# OpAmp_CCCV_Regulator_2026_1_2_A.net
KiCad netlist of a schematic drawn in EAGLE
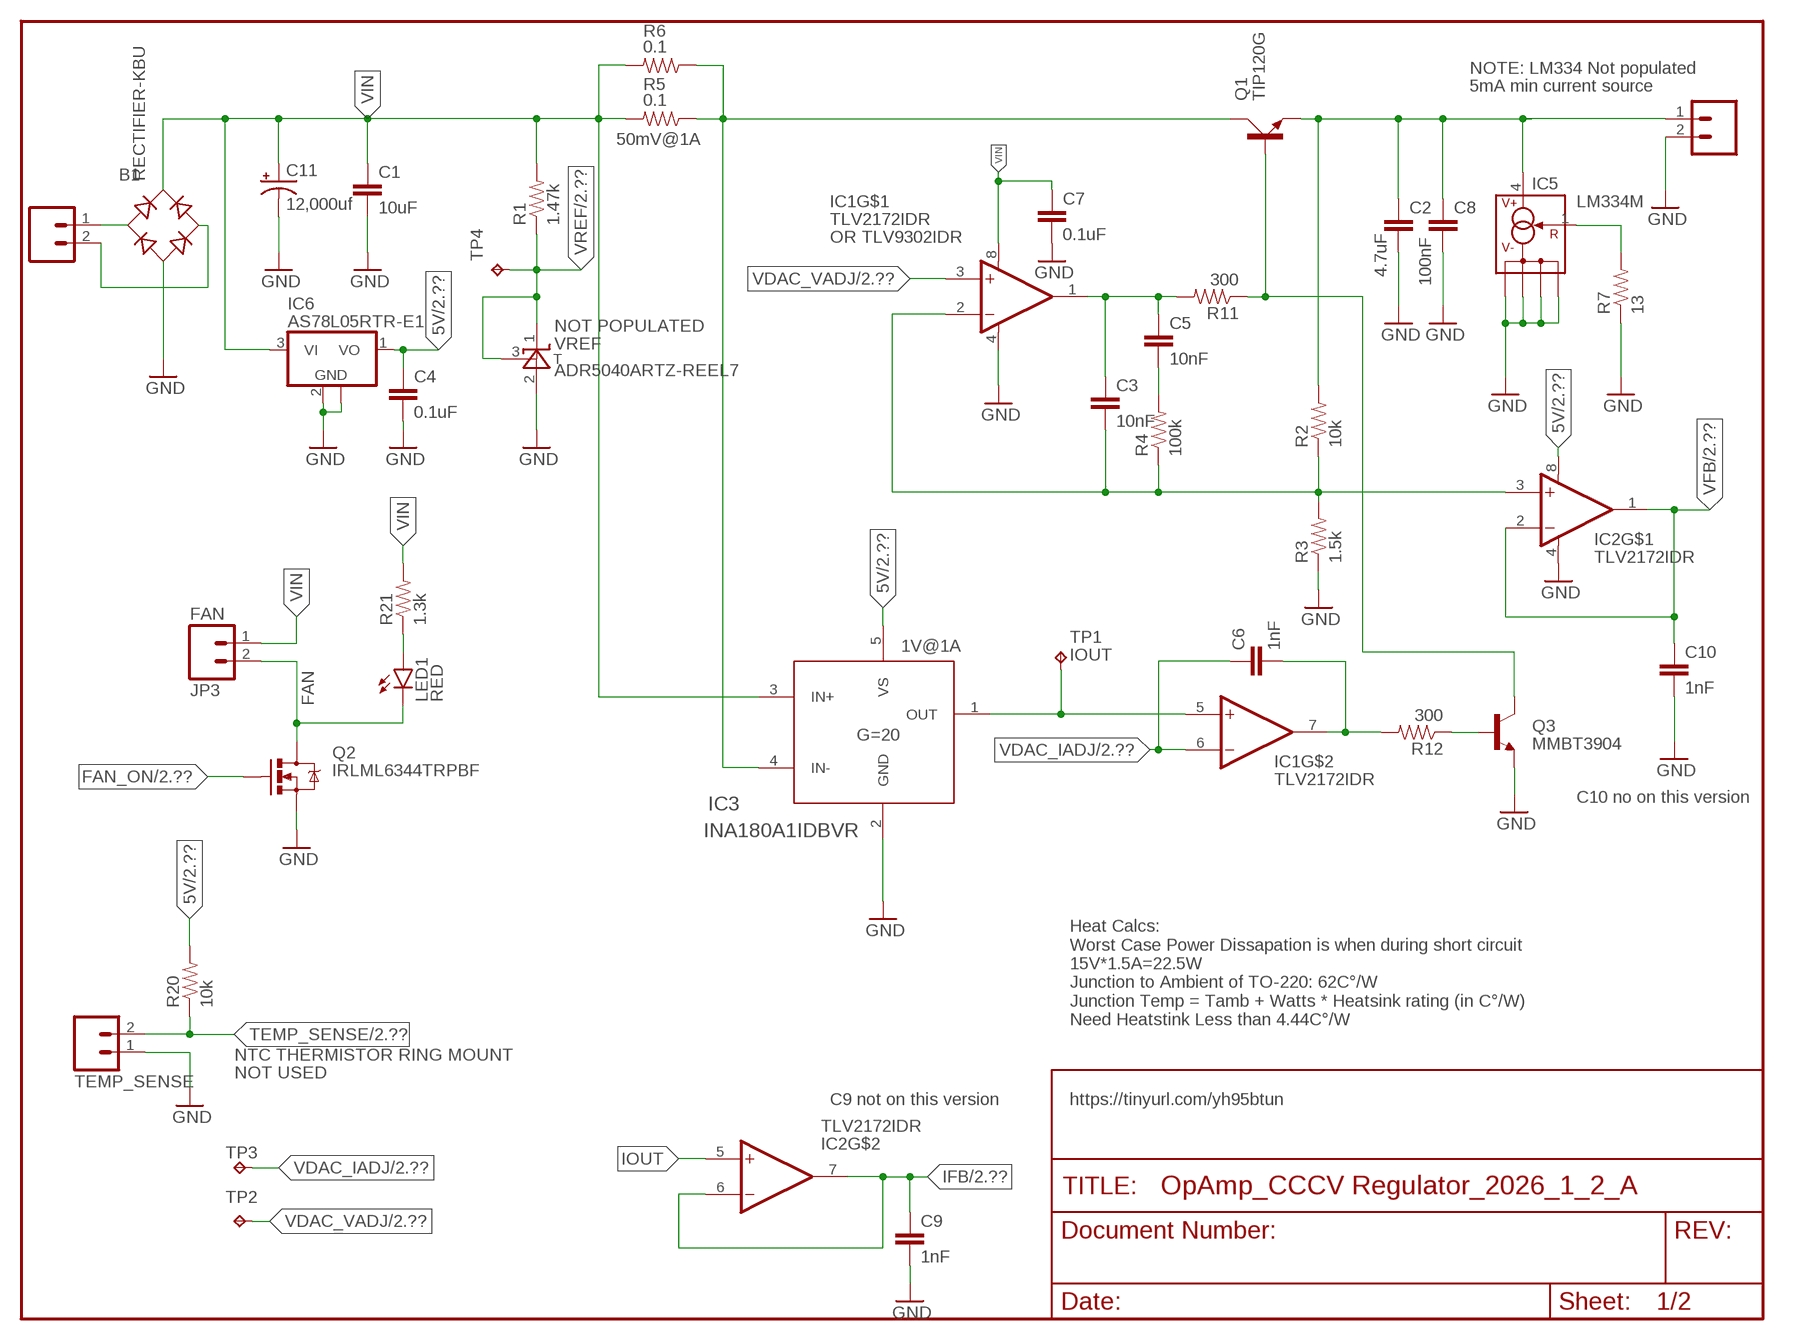
[diagram p0: schematic, sheet 1]
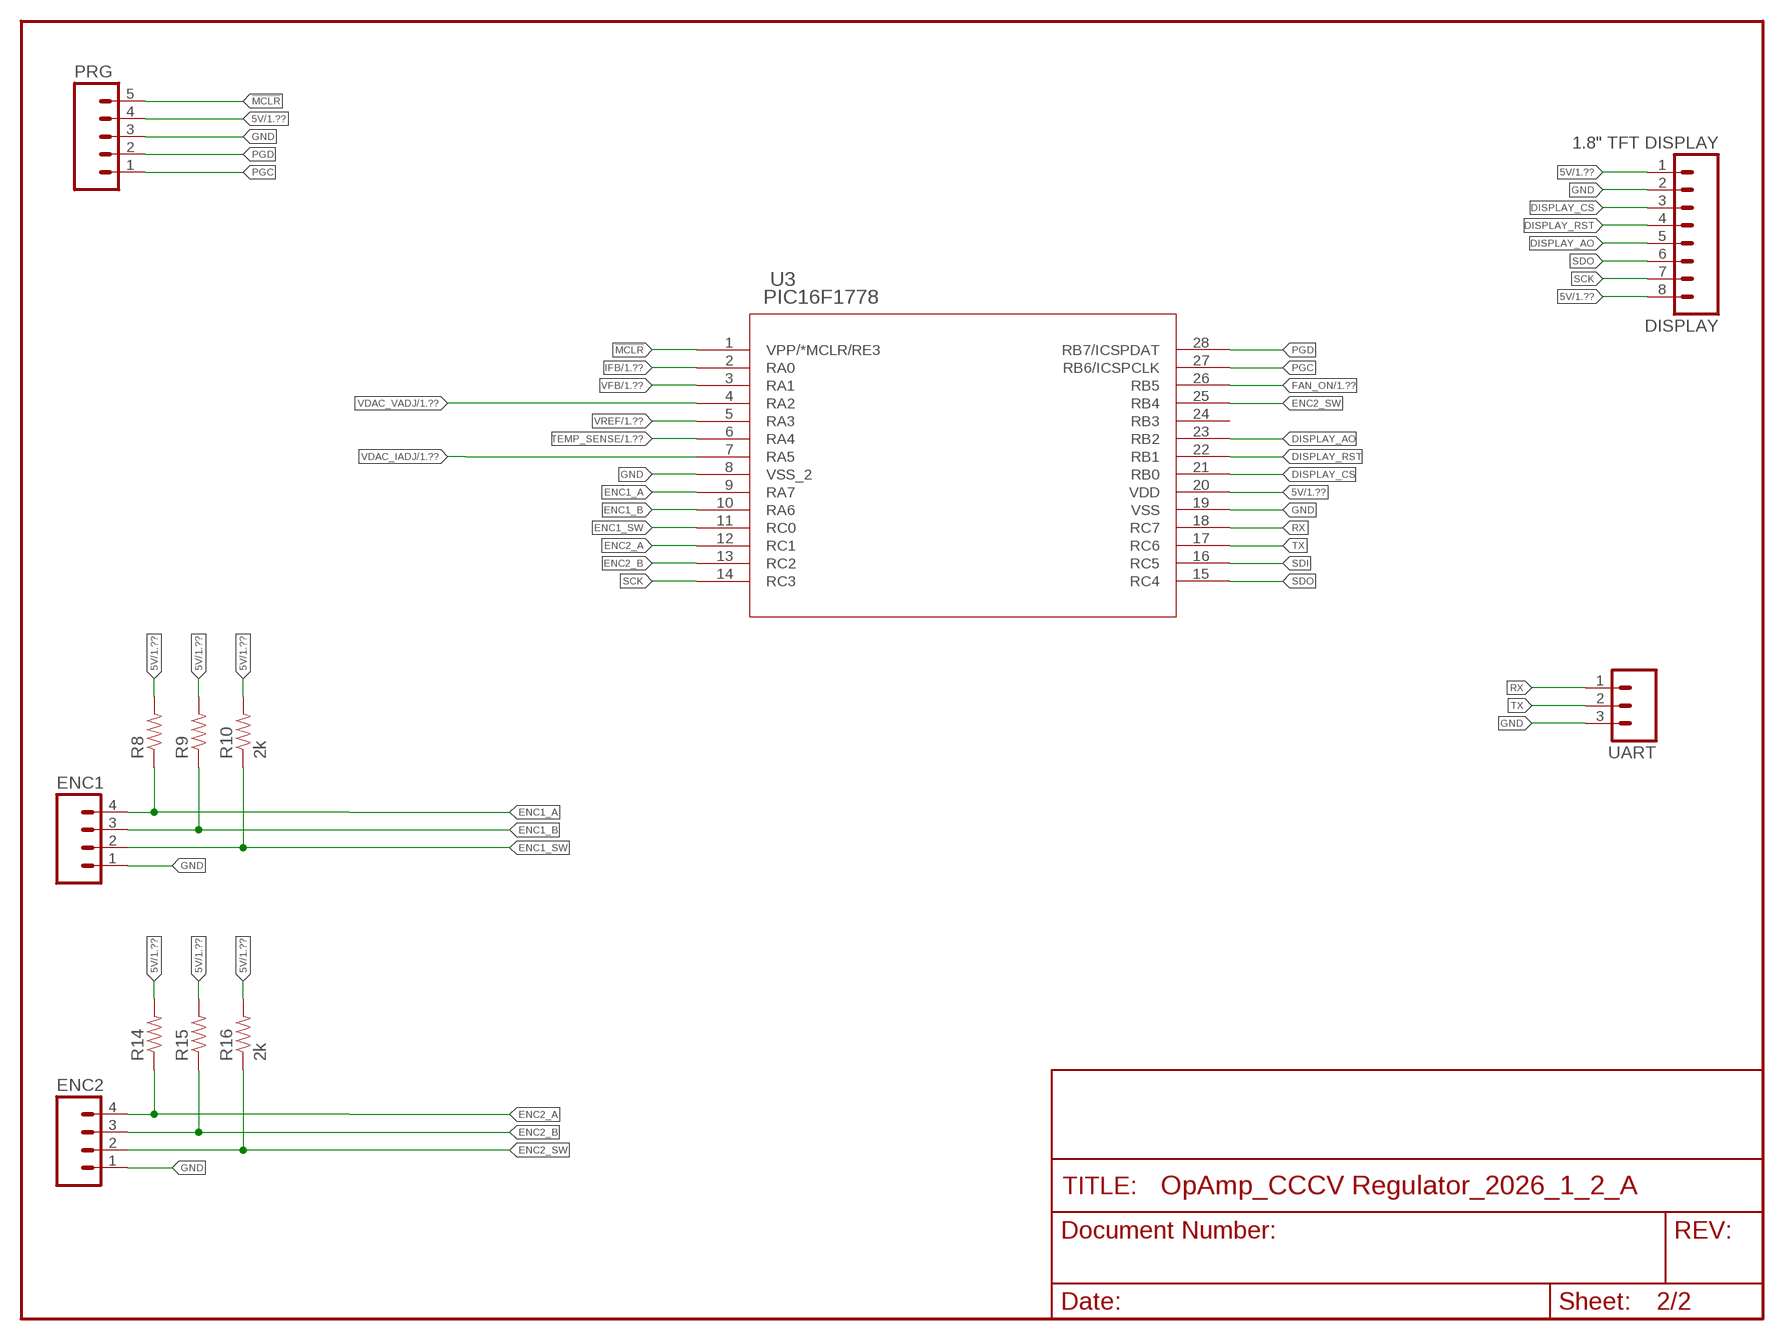
[diagram p1: schematic, sheet 2]

(export (version "E")
  (design (tool "Eeschema 10.0.6"))
  (components
    (comp (ref "DISPLAY")
      (value "1.8\" TFT DISPLAY")
      (footprint "eagle-import:1X08_LOCK_LONGPADS")
      (libsource (lib "eagle-import") (part "M08LOCK_LONGPADS"))
    )
    (comp (ref "ENC1")
      (value "M04LOCK_LONGPADS")
      (footprint "eagle-import:1X04_LOCK_LONGPADS")
      (libsource (lib "eagle-import") (part "M04LOCK_LONGPADS"))
    )
    (comp (ref "ENC2")
      (value "M04LOCK_LONGPADS")
      (footprint "eagle-import:1X04_LOCK_LONGPADS")
      (libsource (lib "eagle-import") (part "M04LOCK_LONGPADS"))
    )
    (comp (ref "PRG")
      (value "M05LOCK")
      (footprint "eagle-import:1X05_LOCK")
      (libsource (lib "eagle-import") (part "M05LOCK"))
    )
    (comp (ref "R8")
      (value "2k")
      (footprint "eagle-import:0805")
      (libsource (lib "eagle-import") (part "SparkFun-Resistors_RESISTOR0805-RES"))
    )
    (comp (ref "R9")
      (value "2k")
      (footprint "eagle-import:0805")
      (libsource (lib "eagle-import") (part "SparkFun-Resistors_RESISTOR0805-RES"))
    )
    (comp (ref "R10")
      (value "2k")
      (footprint "eagle-import:0805")
      (libsource (lib "eagle-import") (part "SparkFun-Resistors_RESISTOR0805-RES"))
    )
    (comp (ref "R14")
      (value "2k")
      (footprint "eagle-import:0805")
      (libsource (lib "eagle-import") (part "SparkFun-Resistors_RESISTOR0805-RES"))
    )
    (comp (ref "R15")
      (value "2k")
      (footprint "eagle-import:0805")
      (libsource (lib "eagle-import") (part "SparkFun-Resistors_RESISTOR0805-RES"))
    )
    (comp (ref "R16")
      (value "2k")
      (footprint "eagle-import:0805")
      (libsource (lib "eagle-import") (part "SparkFun-Resistors_RESISTOR0805-RES"))
    )
    (comp (ref "U3")
      (value "PIC16F1778")
      (footprint "eagle-import:SOIC28-W_MC")
      (fields
        (field (name "MANUFACTURER_PART_NUMBER") "pic16f1773-x/so")
        (field (name "COPYRIGHT") "Copyright (C) 2016 Accelerated Designs. All rights reserved")
      )
      (libsource (lib "eagle-import") (part "PIC16F1773-X/SO"))
    )
    (comp (ref "UART")
      (value "M03LOCK_LONGPADS")
      (footprint "eagle-import:1X03_LOCK_LONGPADS")
      (libsource (lib "eagle-import") (part "M03LOCK_LONGPADS"))
    )
    (comp (ref "B1")
      (value "RECTIFIER-KBU")
      (footprint "eagle-import:KBU")
      (libsource (lib "eagle-import") (part "RECTIFIER-KBU"))
    )
    (comp (ref "C1")
      (value "10uF")
      (footprint "eagle-import:1206")
      (libsource (lib "eagle-import") (part "SparkFun-Capacitors_CAP1206"))
    )
    (comp (ref "C2")
      (value "4.7uF")
      (footprint "eagle-import:1206")
      (libsource (lib "eagle-import") (part "SparkFun-Capacitors_CAP1206"))
    )
    (comp (ref "C3")
      (value "10nF")
      (footprint "eagle-import:0805")
      (libsource (lib "eagle-import") (part "CAP0805"))
    )
    (comp (ref "C4")
      (value "0.1uF")
      (footprint "eagle-import:1206")
      (libsource (lib "eagle-import") (part "SparkFun-Capacitors_CAP1206"))
    )
    (comp (ref "C5")
      (value "10nF")
      (footprint "eagle-import:0805")
      (libsource (lib "eagle-import") (part "CAP0805"))
    )
    (comp (ref "C6")
      (value "1nF")
      (footprint "eagle-import:0805")
      (libsource (lib "eagle-import") (part "CAP0805"))
    )
    (comp (ref "C7")
      (value "0.1uF")
      (footprint "eagle-import:0805")
      (libsource (lib "eagle-import") (part "CAP0805"))
    )
    (comp (ref "C8")
      (value "100nF")
      (footprint "eagle-import:1206")
      (libsource (lib "eagle-import") (part "SparkFun-Capacitors_CAP1206"))
    )
    (comp (ref "C9")
      (value "1nF")
      (footprint "eagle-import:0805")
      (libsource (lib "eagle-import") (part "CAP0805"))
    )
    (comp (ref "C10")
      (value "1nF")
      (footprint "eagle-import:0805")
      (libsource (lib "eagle-import") (part "CAP0805"))
    )
    (comp (ref "C11")
      (value "12,000uf")
      (footprint "eagle-import:EB25D")
      (libsource (lib "eagle-import") (part "CPOL-USE10-25"))
    )
    (comp (ref "IC1")
      (value "TLV2172IDR")
      (footprint "eagle-import:SOIC8")
      (libsource (lib "eagle-import") (part "TLV2171IDR"))
    )
    (comp (ref "IC2")
      (value "TLV2172IDR")
      (footprint "eagle-import:SOIC8")
      (libsource (lib "eagle-import") (part "TLV2171IDR"))
    )
    (comp (ref "IC3")
      (value "INA180A1IDBVR")
      (footprint "eagle-import:DBV0005A_N")
      (fields (field (name "MANUFACTURER") "Texas Instruments"))
      (libsource (lib "eagle-import") (part "INA180A1IDBVR"))
    )
    (comp (ref "IC5")
      (value "LM334M")
      (footprint "eagle-import:SO08")
      (libsource (lib "eagle-import") (part "LM334M"))
    )
    (comp (ref "IC6")
      (value "AS78L05RTR-E1")
      (footprint "eagle-import:SOT89")
      (libsource (lib "eagle-import") (part "78LF05"))
    )
    (comp (ref "JP1")
      (value "M023.5MM_LOCK")
      (footprint "eagle-import:SCREWTERMINAL-3.5MM-2_LOCK")
      (libsource (lib "eagle-import") (part "M023.5MM_LOCK"))
    )
    (comp (ref "JP2")
      (value "M023.5MM")
      (footprint "eagle-import:SCREWTERMINAL-3.5MM-2")
      (libsource (lib "eagle-import") (part "M023.5MM"))
    )
    (comp (ref "JP3")
      (value "FAN")
      (footprint "eagle-import:MOLEX-1X2_LOCK")
      (libsource (lib "eagle-import") (part "M02POLAR_LOCK"))
    )
    (comp (ref "JP4")
      (value "TEMP_SENSE")
      (footprint "eagle-import:1X02")
      (libsource (lib "eagle-import") (part "M02PTH"))
    )
    (comp (ref "LED1")
      (value "RED")
      (footprint "eagle-import:LED-1206")
      (libsource (lib "eagle-import") (part "LED1206"))
    )
    (comp (ref "Q1")
      (value "TIP120G")
      (footprint "eagle-import:TO220AV")
      (libsource (lib "eagle-import") (part "TIP41C"))
    )
    (comp (ref "Q2")
      (value "IRLML6344TRPBF")
      (footprint "eagle-import:SOT323")
      (libsource (lib "eagle-import") (part "MOSFET-NCHANNEL2N7002PW"))
    )
    (comp (ref "Q3")
      (value "MMBT3904")
      (footprint "eagle-import:SOT23")
      (libsource (lib "eagle-import") (part "TRANSISTOR_NPNSOT23"))
    )
    (comp (ref "R1")
      (value "1.47k")
      (footprint "eagle-import:1206")
      (libsource (lib "eagle-import") (part "SparkFun-Resistors_RESISTOR1206"))
    )
    (comp (ref "R2")
      (value "10k")
      (footprint "eagle-import:1206")
      (libsource (lib "eagle-import") (part "SparkFun-Resistors_RESISTOR1206"))
    )
    (comp (ref "R3")
      (value "1.5k")
      (footprint "eagle-import:1206")
      (libsource (lib "eagle-import") (part "SparkFun-Resistors_RESISTOR1206"))
    )
    (comp (ref "R4")
      (value "100k")
      (footprint "eagle-import:0805")
      (libsource (lib "eagle-import") (part "RESISTOR0805-RES"))
    )
    (comp (ref "R5")
      (value "0.1")
      (footprint "eagle-import:1206")
      (libsource (lib "eagle-import") (part "SparkFun-Resistors_RESISTOR1206"))
    )
    (comp (ref "R6")
      (value "0.1")
      (footprint "eagle-import:1206")
      (libsource (lib "eagle-import") (part "SparkFun-Resistors_RESISTOR1206"))
    )
    (comp (ref "R7")
      (value "13")
      (footprint "eagle-import:1206")
      (libsource (lib "eagle-import") (part "SparkFun-Resistors_RESISTOR1206"))
    )
    (comp (ref "R11")
      (value "300")
      (footprint "eagle-import:0805")
      (libsource (lib "eagle-import") (part "RESISTOR0805-RES"))
    )
    (comp (ref "R12")
      (value "300")
      (footprint "eagle-import:0805")
      (libsource (lib "eagle-import") (part "RESISTOR0805-RES"))
    )
    (comp (ref "R20")
      (value "10k")
      (footprint "eagle-import:1206")
      (libsource (lib "eagle-import") (part "SparkFun-Resistors_RESISTOR1206"))
    )
    (comp (ref "R21")
      (value "1.3k")
      (footprint "eagle-import:1206")
      (libsource (lib "eagle-import") (part "SparkFun-Resistors_RESISTOR1206"))
    )
    (comp (ref "TP1")
      (value "TPTP20R")
      (footprint "eagle-import:TP20R")
      (libsource (lib "eagle-import") (part "TPTP20R"))
    )
    (comp (ref "TP2")
      (value "TPTP20R")
      (footprint "eagle-import:TP20R")
      (libsource (lib "eagle-import") (part "TPTP20R"))
    )
    (comp (ref "TP3")
      (value "TPTP20R")
      (footprint "eagle-import:TP20R")
      (libsource (lib "eagle-import") (part "TPTP20R"))
    )
    (comp (ref "TP4")
      (value "TPTP20R")
      (footprint "eagle-import:TP20R")
      (libsource (lib "eagle-import") (part "TPTP20R"))
    )
    (comp (ref "VREF")
      (value "ADR5040ARTZ-REEL7")
      (footprint "eagle-import:RT_3_ADI")
      (libsource (lib "eagle-import") (part "ADR5040ARTZ-REEL7"))
    )
  )
  (nets
    (net (code "1") (name "5V") (class "Default")
      (node (ref "C4") (pin "1") (pinfunction "1_1") (pintype "passive"))
      (node (ref "DISPLAY") (pin "1") (pinfunction "1_1") (pintype "passive"))
      (node (ref "DISPLAY") (pin "8") (pinfunction "8_8") (pintype "passive"))
      (node (ref "IC2") (pin "8") (pinfunction "V+_8") (pintype "power_in"))
      (node (ref "IC3") (pin "5") (pinfunction "VS_5") (pintype "power_in"))
      (node (ref "IC6") (pin "1") (pinfunction "VO_1") (pintype "passive"))
      (node (ref "PRG") (pin "4") (pinfunction "4_4") (pintype "passive"))
      (node (ref "R10") (pin "2") (pinfunction "2_2") (pintype "passive"))
      (node (ref "R14") (pin "2") (pinfunction "2_2") (pintype "passive"))
      (node (ref "R15") (pin "2") (pinfunction "2_2") (pintype "passive"))
      (node (ref "R16") (pin "2") (pinfunction "2_2") (pintype "passive"))
      (node (ref "R20") (pin "2") (pinfunction "2_2") (pintype "passive"))
      (node (ref "R8") (pin "2") (pinfunction "2_2") (pintype "passive"))
      (node (ref "R9") (pin "2") (pinfunction "2_2") (pintype "passive"))
      (node (ref "U3") (pin "20") (pinfunction "VDD_20") (pintype "power_in"))
    )
    (net (code "2") (name "DISPLAY_AO") (class "Default")
      (node (ref "DISPLAY") (pin "5") (pinfunction "5_5") (pintype "passive"))
      (node (ref "U3") (pin "23") (pinfunction "RB2_23") (pintype "bidirectional"))
    )
    (net (code "3") (name "DISPLAY_CS") (class "Default")
      (node (ref "DISPLAY") (pin "3") (pinfunction "3_3") (pintype "passive"))
      (node (ref "U3") (pin "21") (pinfunction "RB0_21") (pintype "bidirectional"))
    )
    (net (code "4") (name "DISPLAY_RST") (class "Default")
      (node (ref "DISPLAY") (pin "4") (pinfunction "4_4") (pintype "passive"))
      (node (ref "U3") (pin "22") (pinfunction "RB1_22") (pintype "bidirectional"))
    )
    (net (code "5") (name "ENC1_A") (class "Default")
      (node (ref "ENC1") (pin "4") (pinfunction "4_4") (pintype "passive"))
      (node (ref "R8") (pin "1") (pinfunction "1_1") (pintype "passive"))
      (node (ref "U3") (pin "9") (pinfunction "RA7_9") (pintype "bidirectional"))
    )
    (net (code "6") (name "ENC1_B") (class "Default")
      (node (ref "ENC1") (pin "3") (pinfunction "3_3") (pintype "passive"))
      (node (ref "R9") (pin "1") (pinfunction "1_1") (pintype "passive"))
      (node (ref "U3") (pin "10") (pinfunction "RA6_10") (pintype "bidirectional"))
    )
    (net (code "7") (name "ENC1_SW") (class "Default")
      (node (ref "ENC1") (pin "2") (pinfunction "2_2") (pintype "passive"))
      (node (ref "R10") (pin "1") (pinfunction "1_1") (pintype "passive"))
      (node (ref "U3") (pin "11") (pinfunction "RC0_11") (pintype "bidirectional"))
    )
    (net (code "8") (name "ENC2_A") (class "Default")
      (node (ref "ENC2") (pin "4") (pinfunction "4_4") (pintype "passive"))
      (node (ref "R14") (pin "1") (pinfunction "1_1") (pintype "passive"))
      (node (ref "U3") (pin "12") (pinfunction "RC1_12") (pintype "bidirectional"))
    )
    (net (code "9") (name "ENC2_B") (class "Default")
      (node (ref "ENC2") (pin "3") (pinfunction "3_3") (pintype "passive"))
      (node (ref "R15") (pin "1") (pinfunction "1_1") (pintype "passive"))
      (node (ref "U3") (pin "13") (pinfunction "RC2_13") (pintype "bidirectional"))
    )
    (net (code "10") (name "ENC2_SW") (class "Default")
      (node (ref "ENC2") (pin "2") (pinfunction "2_2") (pintype "passive"))
      (node (ref "R16") (pin "1") (pinfunction "1_1") (pintype "passive"))
      (node (ref "U3") (pin "25") (pinfunction "RB4_25") (pintype "bidirectional"))
    )
    (net (code "11") (name "FAN") (class "Default")
      (node (ref "JP3") (pin "2") (pinfunction "2_2") (pintype "passive"))
      (node (ref "LED1") (pin "C") (pinfunction "C_C") (pintype "passive"))
      (node (ref "Q2") (pin "3") (pinfunction "D_3") (pintype "passive"))
    )
    (net (code "12") (name "FAN_ON") (class "Default")
      (node (ref "Q2") (pin "1") (pinfunction "G_1") (pintype "passive"))
      (node (ref "U3") (pin "26") (pinfunction "RB5_26") (pintype "bidirectional"))
    )
    (net (code "13") (name "GND") (class "Default")
      (node (ref "B1") (pin "-") (pinfunction "-_-") (pintype "passive"))
      (node (ref "C1") (pin "2") (pinfunction "2_2") (pintype "passive"))
      (node (ref "C10") (pin "2") (pinfunction "2_2") (pintype "passive"))
      (node (ref "C11") (pin "-") (pinfunction "-_-") (pintype "passive"))
      (node (ref "C2") (pin "2") (pinfunction "2_2") (pintype "passive"))
      (node (ref "C4") (pin "2") (pinfunction "2_2") (pintype "passive"))
      (node (ref "C7") (pin "2") (pinfunction "2_2") (pintype "passive"))
      (node (ref "C8") (pin "2") (pinfunction "2_2") (pintype "passive"))
      (node (ref "C9") (pin "2") (pinfunction "2_2") (pintype "passive"))
      (node (ref "DISPLAY") (pin "2") (pinfunction "2_2") (pintype "passive"))
      (node (ref "ENC1") (pin "1") (pinfunction "1_1") (pintype "passive"))
      (node (ref "ENC2") (pin "1") (pinfunction "1_1") (pintype "passive"))
      (node (ref "IC1") (pin "4") (pinfunction "V-_4") (pintype "power_in"))
      (node (ref "IC2") (pin "4") (pinfunction "V-_4") (pintype "power_in"))
      (node (ref "IC3") (pin "2") (pinfunction "GND_2") (pintype "power_in"))
      (node (ref "IC5") (pin "2") (pinfunction "V-_2") (pintype "passive"))
      (node (ref "IC5") (pin "3") (pinfunction "V-_3") (pintype "passive"))
      (node (ref "IC5") (pin "6") (pinfunction "V-_6") (pintype "passive"))
      (node (ref "IC5") (pin "7") (pinfunction "V-_7") (pintype "passive"))
      (node (ref "IC6") (pin "2") (pinfunction "GND_2") (pintype "passive"))
      (node (ref "IC6") (pin "2@1") (pinfunction "GND_2@1") (pintype "passive"))
      (node (ref "JP2") (pin "2") (pinfunction "2_2") (pintype "passive"))
      (node (ref "JP4") (pin "1") (pinfunction "1_1") (pintype "passive"))
      (node (ref "PRG") (pin "3") (pinfunction "3_3") (pintype "passive"))
      (node (ref "Q2") (pin "2") (pinfunction "S_2") (pintype "passive"))
      (node (ref "Q3") (pin "2") (pinfunction "E_2") (pintype "passive"))
      (node (ref "R3") (pin "1") (pinfunction "1_1") (pintype "passive"))
      (node (ref "R7") (pin "1") (pinfunction "1_1") (pintype "passive"))
      (node (ref "U3") (pin "19") (pinfunction "VSS_19") (pintype "power_in"))
      (node (ref "U3") (pin "8") (pinfunction "VSS_2_8") (pintype "power_in"))
      (node (ref "UART") (pin "3") (pinfunction "3_3") (pintype "passive"))
      (node (ref "VREF") (pin "2") (pinfunction "A_2") (pintype "output"))
    )
    (net (code "14") (name "IFB") (class "Default")
      (node (ref "C9") (pin "1") (pinfunction "1_1") (pintype "passive"))
      (node (ref "IC2") (pin "6") (pinfunction "-IN_6") (pintype "input"))
      (node (ref "IC2") (pin "7") (pinfunction "OUT_7") (pintype "output"))
      (node (ref "U3") (pin "2") (pinfunction "RA0_2") (pintype "bidirectional"))
    )
    (net (code "15") (name "IOUT") (class "Default")
      (node (ref "IC1") (pin "5") (pinfunction "+IN_5") (pintype "input"))
      (node (ref "IC2") (pin "5") (pinfunction "+IN_5") (pintype "input"))
      (node (ref "IC3") (pin "1") (pinfunction "OUT_1") (pintype "output"))
      (node (ref "TP1") (pin "TP") (pinfunction "TP_TP") (pintype "input"))
    )
    (net (code "16") (name "Net-(B1-PadAC1)") (class "Default")
      (node (ref "B1") (pin "AC1") (pinfunction "AC1_AC1") (pintype "passive"))
      (node (ref "JP1") (pin "1") (pinfunction "1_1") (pintype "passive"))
    )
    (net (code "17") (name "Net-(B1-PadAC2)") (class "Default")
      (node (ref "B1") (pin "AC2") (pinfunction "AC2_AC2") (pintype "passive"))
      (node (ref "JP1") (pin "2") (pinfunction "2_2") (pintype "passive"))
    )
    (net (code "18") (name "Net-(C5-Pad2)") (class "Default")
      (node (ref "C5") (pin "2") (pinfunction "2_2") (pintype "passive"))
      (node (ref "R4") (pin "2") (pinfunction "2_2") (pintype "passive"))
    )
    (net (code "19") (name "Net-(IC1A--IN)") (class "Default")
      (node (ref "C3") (pin "2") (pinfunction "2_2") (pintype "passive"))
      (node (ref "IC1") (pin "2") (pinfunction "-IN_2") (pintype "input"))
      (node (ref "IC2") (pin "3") (pinfunction "+IN_3") (pintype "input"))
      (node (ref "R2") (pin "1") (pinfunction "1_1") (pintype "passive"))
      (node (ref "R3") (pin "2") (pinfunction "2_2") (pintype "passive"))
      (node (ref "R4") (pin "1") (pinfunction "1_1") (pintype "passive"))
    )
    (net (code "20") (name "Net-(IC1A-OUT)") (class "Default")
      (node (ref "C3") (pin "1") (pinfunction "1_1") (pintype "passive"))
      (node (ref "C5") (pin "1") (pinfunction "1_1") (pintype "passive"))
      (node (ref "IC1") (pin "1") (pinfunction "OUT_1") (pintype "output"))
      (node (ref "R11") (pin "2") (pinfunction "2_2") (pintype "passive"))
    )
    (net (code "21") (name "Net-(IC1B-OUT)") (class "Default")
      (node (ref "C6") (pin "2") (pinfunction "2_2") (pintype "passive"))
      (node (ref "IC1") (pin "7") (pinfunction "OUT_7") (pintype "output"))
      (node (ref "R12") (pin "2") (pinfunction "2_2") (pintype "passive"))
    )
    (net (code "22") (name "Net-(IC3-IN-)") (class "Default")
      (node (ref "IC3") (pin "4") (pinfunction "IN-_4") (pintype "input"))
      (node (ref "Q1") (pin "C") (pinfunction "C_C") (pintype "passive"))
      (node (ref "R5") (pin "1") (pinfunction "1_1") (pintype "passive"))
      (node (ref "R6") (pin "1") (pinfunction "1_1") (pintype "passive"))
    )
    (net (code "23") (name "Net-(IC5-R)") (class "Default")
      (node (ref "IC5") (pin "1") (pinfunction "R_1") (pintype "passive"))
      (node (ref "R7") (pin "2") (pinfunction "2_2") (pintype "passive"))
    )
    (net (code "24") (name "Net-(IC5-V+)") (class "Default")
      (node (ref "C2") (pin "1") (pinfunction "1_1") (pintype "passive"))
      (node (ref "C8") (pin "1") (pinfunction "1_1") (pintype "passive"))
      (node (ref "IC5") (pin "4") (pinfunction "V+_4") (pintype "passive"))
      (node (ref "JP2") (pin "1") (pinfunction "1_1") (pintype "passive"))
      (node (ref "Q1") (pin "E") (pinfunction "E_E") (pintype "passive"))
      (node (ref "R2") (pin "2") (pinfunction "2_2") (pintype "passive"))
    )
    (net (code "25") (name "Net-(LED1-PadA)") (class "Default")
      (node (ref "LED1") (pin "A") (pinfunction "A_A") (pintype "passive"))
      (node (ref "R21") (pin "1") (pinfunction "1_1") (pintype "passive"))
    )
    (net (code "26") (name "Net-(Q3-B)") (class "Default")
      (node (ref "Q3") (pin "1") (pinfunction "B_1") (pintype "passive"))
      (node (ref "R12") (pin "1") (pinfunction "1_1") (pintype "passive"))
    )
    (net (code "27") (name "Net-(Q3-C)") (class "Default")
      (node (ref "Q1") (pin "B") (pinfunction "B_B") (pintype "passive"))
      (node (ref "Q3") (pin "3") (pinfunction "C_3") (pintype "passive"))
      (node (ref "R11") (pin "1") (pinfunction "1_1") (pintype "passive"))
    )
    (net (code "28") (name "PGC") (class "Default")
      (node (ref "PRG") (pin "1") (pinfunction "1_1") (pintype "passive"))
      (node (ref "U3") (pin "27") (pinfunction "RB6/ICSPCLK_27") (pintype "bidirectional"))
    )
    (net (code "29") (name "PGD") (class "Default")
      (node (ref "PRG") (pin "2") (pinfunction "2_2") (pintype "passive"))
      (node (ref "U3") (pin "28") (pinfunction "RB7/ICSPDAT_28") (pintype "bidirectional"))
    )
    (net (code "30") (name "RX") (class "Default")
      (node (ref "U3") (pin "18") (pinfunction "RC7_18") (pintype "bidirectional"))
      (node (ref "UART") (pin "1") (pinfunction "1_1") (pintype "passive"))
    )
    (net (code "31") (name "SCK") (class "Default")
      (node (ref "DISPLAY") (pin "7") (pinfunction "7_7") (pintype "passive"))
      (node (ref "U3") (pin "14") (pinfunction "RC3_14") (pintype "bidirectional"))
    )
    (net (code "32") (name "SDI") (class "Default")
      (node (ref "U3") (pin "16") (pinfunction "RC5_16") (pintype "bidirectional"))
    )
    (net (code "33") (name "SDO") (class "Default")
      (node (ref "DISPLAY") (pin "6") (pinfunction "6_6") (pintype "passive"))
      (node (ref "U3") (pin "15") (pinfunction "RC4_15") (pintype "bidirectional"))
    )
    (net (code "34") (name "TEMP_SENSE") (class "Default")
      (node (ref "JP4") (pin "2") (pinfunction "2_2") (pintype "passive"))
      (node (ref "R20") (pin "1") (pinfunction "1_1") (pintype "passive"))
      (node (ref "U3") (pin "6") (pinfunction "RA4_6") (pintype "bidirectional"))
    )
    (net (code "35") (name "TX") (class "Default")
      (node (ref "U3") (pin "17") (pinfunction "RC6_17") (pintype "bidirectional"))
      (node (ref "UART") (pin "2") (pinfunction "2_2") (pintype "passive"))
    )
    (net (code "36") (name "VDAC_IADJ") (class "Default")
      (node (ref "C6") (pin "1") (pinfunction "1_1") (pintype "passive"))
      (node (ref "IC1") (pin "6") (pinfunction "-IN_6") (pintype "input"))
      (node (ref "TP3") (pin "TP") (pinfunction "TP_TP") (pintype "input"))
      (node (ref "U3") (pin "7") (pinfunction "RA5_7") (pintype "bidirectional"))
    )
    (net (code "37") (name "VDAC_VADJ") (class "Default")
      (node (ref "IC1") (pin "3") (pinfunction "+IN_3") (pintype "input"))
      (node (ref "TP2") (pin "TP") (pinfunction "TP_TP") (pintype "input"))
      (node (ref "U3") (pin "4") (pinfunction "RA2_4") (pintype "bidirectional"))
    )
    (net (code "38") (name "VFB") (class "Default")
      (node (ref "C10") (pin "1") (pinfunction "1_1") (pintype "passive"))
      (node (ref "IC2") (pin "1") (pinfunction "OUT_1") (pintype "output"))
      (node (ref "IC2") (pin "2") (pinfunction "-IN_2") (pintype "input"))
      (node (ref "U3") (pin "3") (pinfunction "RA1_3") (pintype "bidirectional"))
    )
    (net (code "39") (name "VIN") (class "Default")
      (node (ref "B1") (pin "+") (pinfunction "+_+") (pintype "passive"))
      (node (ref "C1") (pin "1") (pinfunction "1_1") (pintype "passive"))
      (node (ref "C11") (pin "+") (pinfunction "+_+") (pintype "passive"))
      (node (ref "C7") (pin "1") (pinfunction "1_1") (pintype "passive"))
      (node (ref "IC1") (pin "8") (pinfunction "V+_8") (pintype "power_in"))
      (node (ref "IC3") (pin "3") (pinfunction "IN+_3") (pintype "input"))
      (node (ref "IC6") (pin "3") (pinfunction "VI_3") (pintype "input"))
      (node (ref "JP3") (pin "1") (pinfunction "1_1") (pintype "passive"))
      (node (ref "R1") (pin "2") (pinfunction "2_2") (pintype "passive"))
      (node (ref "R21") (pin "2") (pinfunction "2_2") (pintype "passive"))
      (node (ref "R5") (pin "2") (pinfunction "2_2") (pintype "passive"))
      (node (ref "R6") (pin "2") (pinfunction "2_2") (pintype "passive"))
    )
    (net (code "40") (name "VREF") (class "Default")
      (node (ref "R1") (pin "1") (pinfunction "1_1") (pintype "passive"))
      (node (ref "TP4") (pin "TP") (pinfunction "TP_TP") (pintype "input"))
      (node (ref "U3") (pin "5") (pinfunction "RA3_5") (pintype "bidirectional"))
      (node (ref "VREF") (pin "1") (pinfunction "C_1") (pintype "input"))
      (node (ref "VREF") (pin "3") (pinfunction "T_3") (pintype "power_in"))
    )
    (net (code "41") (name "unconnected-(U3-RB3-Pad24)") (class "Default")
      (node (ref "U3") (pin "24") (pinfunction "RB3_24") (pintype "bidirectional"))
    )
    (net (code "42") (name "~{MCLR}") (class "Default")
      (node (ref "PRG") (pin "5") (pinfunction "5_5") (pintype "passive"))
      (node (ref "U3") (pin "1") (pinfunction "VPP/*MCLR/RE3_1") (pintype "bidirectional"))
    )
  )
)
